# Bluetooth.net
KiCad netlist of a schematic drawn in Altium Designer
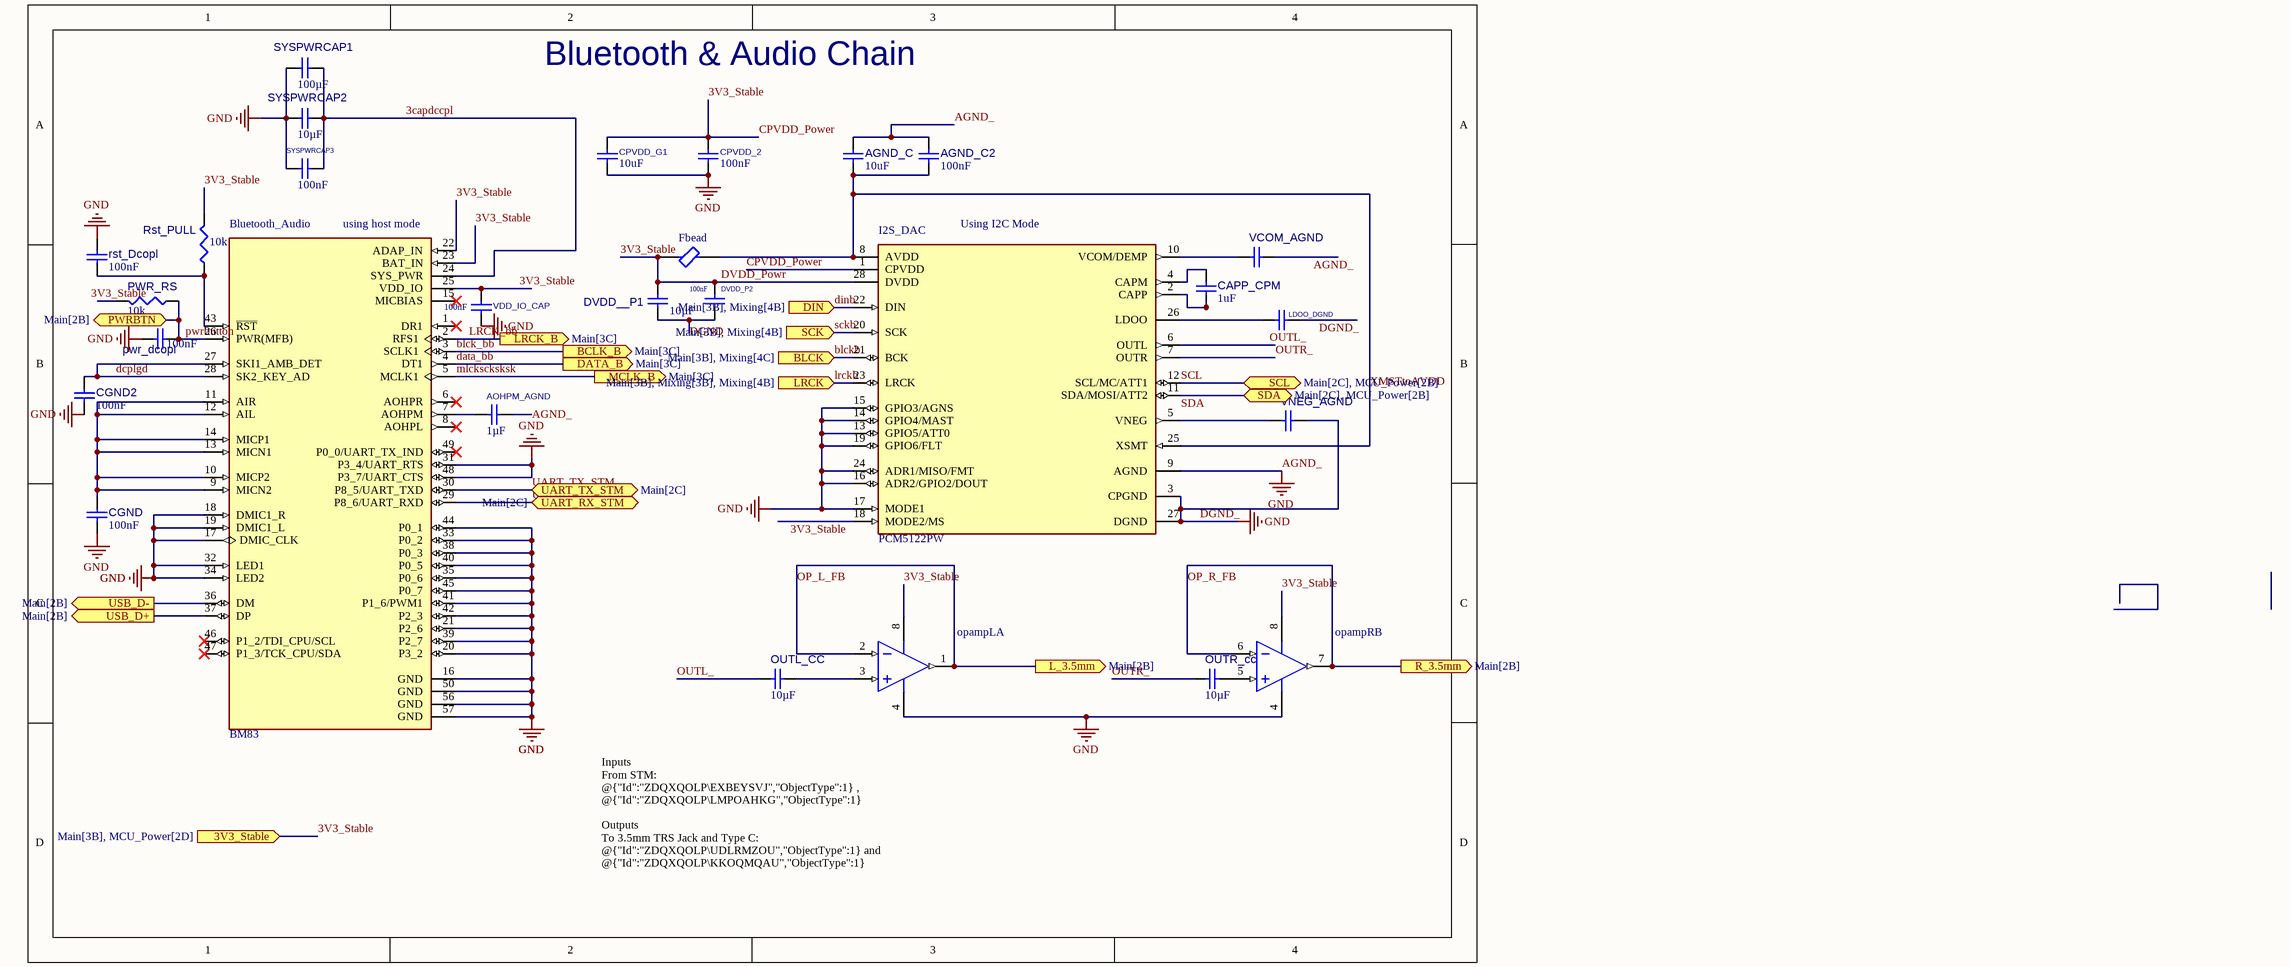
[diagram p0: Bluetooth.SchDoc]

(export (version "E")
  (design (tool "Eeschema 10.0.6"))
  (components
    (comp (ref "AGND_C")
      (value "10uF")
      (footprint "CAPC1005X56X25LL10T15")
      (description "Chip Capacitor, 0.1 uF, +/- 5%, 16 V, 0402 (1005 Metric)")
      (fields (field (name "TOLERANCE") "5%") (field (name "Comment") "Capacitor 0.1 uF +/- 5% 16 V 0402"))
      (libsource (lib "Sripathy Siddartha") (part "CAP-NP-2"))
    )
    (comp (ref "AGND_C2")
      (value "100nF")
      (footprint "CAPC0402(1005)60_L")
      (description "Chip Capacitor, 100nF +/-20%, 10V, 0402, Thickness 0.6 mm")
      (fields (field (name "TOLERANCE") "20%") (field (name "Comment") "Capacitor 100nF +/-20% 10V 0402"))
      (libsource (lib "Sripathy Siddartha") (part "CAP-NP-2"))
    )
    (comp (ref "AOHPM_AGND")
      (value "1µF")
      (footprint "CAPC2013X145X50ML20T25")
      (description "Chip Capacitor, 1 uF, +/-10%, 25 V, 0805 (2012 Metric)")
      (fields (field (name "TOLERANCE") "10%") (field (name "Comment") "Capacitor 1 uF +/- 10% 25 V 0805"))
      (libsource (lib "Sripathy Siddartha") (part "CAP-NP-2"))
    )
    (comp (ref "Bluetooth_Audio")
      (value "BM83")
      (footprint "XCVR_BM83SM1-00AA")
      (description "Bluetooth Bluetooth v5.0 Transceiver Module 2.4GHz ~ 2.48GHz PCB Trace Surface Mount")
      (fields (field (name "MP") "BM83SM1-00AA") (field (name "MF") "Microchip Technology"))
      (libsource (lib "Sripathy Siddartha") (part "BM83SM1-00AA"))
    )
    (comp (ref "CAPP_CPM")
      (value "1uF")
      (footprint "CAPC1005X56X25LL10T15")
      (description "Chip Capacitor, 0.1 uF, +/- 5%, 16 V, 0402 (1005 Metric)")
      (fields (field (name "TOLERANCE") "5%") (field (name "Comment") "Capacitor 0.1 uF +/- 5% 16 V 0402"))
      (libsource (lib "Sripathy Siddartha") (part "CAP-NP-2"))
    )
    (comp (ref "CGND")
      (value "100nF")
      (footprint "CAPC0402(1005)60_L")
      (description "Chip Capacitor, 100nF +/-20%, 10V, 0402, Thickness 0.6 mm")
      (fields (field (name "TOLERANCE") "20%") (field (name "Comment") "Capacitor 100nF +/-20% 10V 0402"))
      (libsource (lib "Sripathy Siddartha") (part "CAP-NP-2"))
    )
    (comp (ref "CGND2")
      (value "100nF")
      (footprint "CAPC0402(1005)60_L")
      (description "Chip Capacitor, 100nF +/-20%, 10V, 0402, Thickness 0.6 mm")
      (fields (field (name "TOLERANCE") "20%") (field (name "Comment") "Capacitor 100nF +/-20% 10V 0402"))
      (libsource (lib "Sripathy Siddartha") (part "CAP-NP-2"))
    )
    (comp (ref "CPVDD_2")
      (value "100nF")
      (footprint "CAPC0402(1005)60_L")
      (description "Chip Capacitor, 100nF +/-20%, 10V, 0402, Thickness 0.6 mm")
      (fields (field (name "TOLERANCE") "20%") (field (name "Comment") "Capacitor 100nF +/-20% 10V 0402"))
      (libsource (lib "Sripathy Siddartha") (part "CAP-NP-2"))
    )
    (comp (ref "CPVDD_G1")
      (value "10uF")
      (footprint "CAPC1005X56X25LL10T15")
      (description "Chip Capacitor, 0.1 uF, +/- 5%, 16 V, 0402 (1005 Metric)")
      (fields (field (name "TOLERANCE") "5%") (field (name "Comment") "Capacitor 0.1 uF +/- 5% 16 V 0402"))
      (libsource (lib "Sripathy Siddartha") (part "CAP-NP-2"))
    )
    (comp (ref "DVDD_P2")
      (value "100nF")
      (footprint "CAPC0402(1005)60_L")
      (description "Chip Capacitor, 100nF +/-20%, 10V, 0402, Thickness 0.6 mm")
      (fields (field (name "TOLERANCE") "20%") (field (name "Comment") "Capacitor 100nF +/-20% 10V 0402"))
      (libsource (lib "Sripathy Siddartha") (part "CAP-NP-2"))
    )
    (comp (ref "DVDD__P1")
      (value "10µF")
      (footprint "CAPC3216X180X50NL20T25")
      (description "Chip Capacitor, 10 uF, +/- 10%, 16 V, 1206 (3216 Metric)")
      (fields (field (name "TOLERANCE") "10%") (field (name "Comment") "Capacitor 10 uF +/- 10% 16 V 1206"))
      (libsource (lib "Sripathy Siddartha") (part "CAP-NP-2"))
    )
    (comp (ref "Fbead")
      (value "NFZ32BW3R6HZ10L")
      (footprint "FP-NFZ32BW-w2_8-MFG")
      (description "Ferrite Bead 3.6Ω @ 1MHz ±30% 2.55A 0.036Ω 1210 Embossed T/R")
      (libsource (lib "Altium Content Vault") (part "5f30dd21d616792df468990f7003faa"))
    )
    (comp (ref "I2S_DAC")
      (value "PCM5122PW")
      (footprint "FP-PW0028A-IPC_C")
      (description "IC DAC 16/24/32BIT 384K 28TSSOP")
      (libsource (lib "Altium Content Vault") (part "6849a3bd1951d5a6b717c470419a4c4"))
    )
    (comp (ref "LDOO_DGND")
      (value "Capacitor 0.1 uF +/- 5% 16 V 0402")
      (footprint "CAPC1005X56X25LL10T15")
      (description "Chip Capacitor, 0.1 uF, +/- 5%, 16 V, 0402 (1005 Metric)")
      (fields (field (name "TOLERANCE") "5%"))
      (libsource (lib "Sripathy Siddartha") (part "CAP-NP-2"))
    )
    (comp (ref "opampL")
      (value "OPA1612AIDR")
      (footprint "D0008A_N")
      (fields (field (name "MANUFACTURER") "Texas Instruments"))
      (libsource (lib "Altium Content Vault") (part "TI-OPA1612D8"))
    )
    (comp (ref "opampR")
      (value "OPA1612AIDR")
      (footprint "D0008A_N")
      (fields (field (name "MANUFACTURER") "Texas Instruments"))
      (libsource (lib "Altium Content Vault") (part "TI-OPA1612D8"))
    )
    (comp (ref "OUTL_CC")
      (value "10µF")
      (footprint "CAPC3216X180X50NL20T25")
      (description "Chip Capacitor, 10 uF, +/- 10%, 16 V, 1206 (3216 Metric)")
      (fields (field (name "TOLERANCE") "10%") (field (name "Comment") "Capacitor 10 uF +/- 10% 16 V 1206"))
      (libsource (lib "Sripathy Siddartha") (part "CAP-NP-2"))
    )
    (comp (ref "OUTR_cc")
      (value "10µF")
      (footprint "CAPC3216X180X50NL20T25")
      (description "Chip Capacitor, 10 uF, +/- 10%, 16 V, 1206 (3216 Metric)")
      (fields (field (name "TOLERANCE") "10%") (field (name "Comment") "Capacitor 10 uF +/- 10% 16 V 1206"))
      (libsource (lib "Sripathy Siddartha") (part "CAP-NP-2"))
    )
    (comp (ref "pwr_dcopl")
      (value "100nF")
      (footprint "CAPC0402(1005)60_L")
      (description "Chip Capacitor, 100nF +/-20%, 10V, 0402, Thickness 0.6 mm")
      (fields (field (name "TOLERANCE") "20%") (field (name "Comment") "Capacitor 100nF +/-20% 10V 0402"))
      (libsource (lib "Sripathy Siddartha") (part "CAP-NP-2"))
    )
    (comp (ref "PWR_RS")
      (value "10k")
      (footprint "RESC0402(1005)_L")
      (description "10K 0.063W 1% 0402 (1005 Metric)  SMD")
      (fields (field (name "POWER") "63mW") (field (name "TOLERANCE") "1%"))
      (libsource (lib "Sripathy Siddartha") (part "10KR2F"))
    )
    (comp (ref "rst_Dcopl")
      (value "100nF")
      (footprint "CAPC0402(1005)60_L")
      (description "Chip Capacitor, 100nF +/-20%, 10V, 0402, Thickness 0.6 mm")
      (fields (field (name "TOLERANCE") "20%") (field (name "Comment") "Capacitor 100nF +/-20% 10V 0402"))
      (libsource (lib "Sripathy Siddartha") (part "CAP-NP-2"))
    )
    (comp (ref "Rst_PULL")
      (value "10k")
      (footprint "RESC0402(1005)_L")
      (description "10K 0.063W 1% 0402 (1005 Metric)  SMD")
      (fields (field (name "POWER") "63mW") (field (name "TOLERANCE") "1%"))
      (libsource (lib "Sripathy Siddartha") (part "10KR2F"))
    )
    (comp (ref "SYSPWRCAP1")
      (value "100µF")
      (footprint "CAPC0805(2012)145_L")
      (description "Chip Capacitor, 100µF +/-20%, 6.3V, 0805, Thickness 1.45 mm")
      (fields (field (name "TOLERANCE") "10%") (field (name "Comment") "Capacitor 100µF +/-20% 6.3V 0805"))
      (libsource (lib "Sripathy Siddartha") (part "CAP-NP-2"))
    )
    (comp (ref "SYSPWRCAP2")
      (value "10µF")
      (footprint "CAPC0805(2012)145_L")
      (description "Chip Capacitor, 10µF +/-20%, 25V, 0805, Thickness 1.45 mm")
      (fields (field (name "TOLERANCE") "10%") (field (name "Comment") "Capacitor 10µF +/-20% 25V 0805"))
      (libsource (lib "Sripathy Siddartha") (part "CAP-NP-2"))
    )
    (comp (ref "SYSPWRCAP3")
      (value "100nF")
      (footprint "CAPC0402(1005)60_L")
      (description "Chip Capacitor, 100nF +/-20%, 50V, 0402, Thickness 0.6 mm")
      (fields (field (name "TOLERANCE") "10%") (field (name "Comment") "Capacitor 100nF +/-20% 50V 0402"))
      (libsource (lib "Sripathy Siddartha") (part "CAP-NP-2"))
    )
    (comp (ref "VCOM_AGND")
      (value "Capacitor 0.1 uF +/- 5% 16 V 0402")
      (footprint "CAPC1005X56X25LL10T15")
      (description "Chip Capacitor, 0.1 uF, +/- 5%, 16 V, 0402 (1005 Metric)")
      (fields (field (name "TOLERANCE") "5%"))
      (libsource (lib "Sripathy Siddartha") (part "CAP-NP-2"))
    )
    (comp (ref "VDD_IO_CAP")
      (value "100nF")
      (footprint "CAPC0402(1005)60_L")
      (description "Chip Capacitor, 100nF +/-20%, 25V, 0402, Thickness 0.6 mm")
      (fields (field (name "TOLERANCE") "10%") (field (name "Comment") "Capacitor 100nF +/-20% 25V 0402"))
      (libsource (lib "Sripathy Siddartha") (part "CAP-NP-2"))
    )
    (comp (ref "VNEG_AGND")
      (value "Capacitor 0.1 uF +/- 5% 16 V 0402")
      (footprint "CAPC1005X56X25LL10T15")
      (description "Chip Capacitor, 0.1 uF, +/- 5%, 16 V, 0402 (1005 Metric)")
      (fields (field (name "TOLERANCE") "5%"))
      (libsource (lib "Sripathy Siddartha") (part "CAP-NP-2"))
    )
  )
  (nets
    (net (code "1") (name "/3V3_Stable") (class "Default")
      (node (ref "Bluetooth_Audio") (pin "22") (pinfunction "ADAP_IN_22") (pintype "input"))
      (node (ref "Bluetooth_Audio") (pin "23") (pinfunction "BAT_IN_23") (pintype "input"))
      (node (ref "Bluetooth_Audio") (pin "25") (pinfunction "VDD_IO_25") (pintype "power_in"))
      (node (ref "CPVDD_2") (pin "2") (pinfunction "2_2") (pintype "passive"))
      (node (ref "CPVDD_G1") (pin "1") (pinfunction "1_1") (pintype "passive"))
      (node (ref "DVDD_P2") (pin "2") (pinfunction "2_2") (pintype "passive"))
      (node (ref "DVDD__P1") (pin "2") (pinfunction "2_2") (pintype "passive"))
      (node (ref "Fbead") (pin "1") (pinfunction "1_1") (pintype "passive"))
      (node (ref "I2S_DAC") (pin "1") (pinfunction "CPVDD_1") (pintype "power_in"))
      (node (ref "I2S_DAC") (pin "18") (pinfunction "MODE2/MS_18") (pintype "input"))
      (node (ref "I2S_DAC") (pin "28") (pinfunction "DVDD_28") (pintype "power_in"))
      (node (ref "Rst_PULL") (pin "2") (pinfunction "2_2") (pintype "passive"))
      (node (ref "VDD_IO_CAP") (pin "2") (pinfunction "2_2") (pintype "passive"))
      (node (ref "opampL") (pin "8") (pinfunction "V+_8") (pintype "power_in"))
      (node (ref "opampR") (pin "8") (pinfunction "V+_8") (pintype "power_in"))
    )
    (net (code "2") (name "/3capdccpl") (class "Default")
      (node (ref "Bluetooth_Audio") (pin "24") (pinfunction "SYS_PWR_24") (pintype "power_in"))
      (node (ref "SYSPWRCAP1") (pin "2") (pinfunction "2_2") (pintype "passive"))
      (node (ref "SYSPWRCAP2") (pin "2") (pinfunction "2_2") (pintype "passive"))
      (node (ref "SYSPWRCAP3") (pin "2") (pinfunction "2_2") (pintype "passive"))
    )
    (net (code "4") (name "/LRCK_bb") (class "Default")
      (node (ref "Bluetooth_Audio") (pin "2") (pinfunction "RFS1_2") (pintype "bidirectional"))
    )
    (net (code "5") (name "/OP_L_FB") (class "Default")
      (node (ref "opampL") (pin "1") (pinfunction "OUT_A_1") (pintype "output"))
      (node (ref "opampL") (pin "2") (pinfunction "IN_A-_2") (pintype "input"))
    )
    (net (code "6") (name "/OP_R_FB") (class "Default")
      (node (ref "opampR") (pin "6") (pinfunction "IN_B-_6") (pintype "input"))
      (node (ref "opampR") (pin "7") (pinfunction "OUT_B_7") (pintype "output"))
    )
    (net (code "7") (name "/OUTL_") (class "Default")
      (node (ref "I2S_DAC") (pin "6") (pinfunction "OUTL_6") (pintype "output"))
      (node (ref "OUTL_CC") (pin "1") (pinfunction "1_1") (pintype "passive"))
    )
    (net (code "8") (name "/OUTR_") (class "Default")
      (node (ref "I2S_DAC") (pin "7") (pinfunction "OUTR_7") (pintype "output"))
      (node (ref "OUTR_cc") (pin "1") (pinfunction "1_1") (pintype "passive"))
    )
    (net (code "9") (name "/SCL") (class "Default")
      (node (ref "I2S_DAC") (pin "12") (pinfunction "SCL/MC/ATT1_12") (pintype "bidirectional"))
    )
    (net (code "10") (name "/SDA") (class "Default")
      (node (ref "I2S_DAC") (pin "11") (pinfunction "SDA/MOSI/ATT2_11") (pintype "bidirectional"))
    )
    (net (code "11") (name "/UART_RX_STM") (class "Default")
      (node (ref "Bluetooth_Audio") (pin "29") (pinfunction "P8_6/UART_RXD_29") (pintype "bidirectional"))
    )
    (net (code "12") (name "/UART_TX_STM") (class "Default")
      (node (ref "Bluetooth_Audio") (pin "30") (pinfunction "P8_5/UART_TXD_30") (pintype "bidirectional"))
    )
    (net (code "13") (name "/USB_D+") (class "Default")
      (node (ref "Bluetooth_Audio") (pin "37") (pinfunction "DP_37") (pintype "bidirectional"))
    )
    (net (code "14") (name "/USB_D-") (class "Default")
      (node (ref "Bluetooth_Audio") (pin "36") (pinfunction "DM_36") (pintype "bidirectional"))
    )
    (net (code "15") (name "/XMSTtoAVDD") (class "Default")
      (node (ref "AGND_C") (pin "1") (pinfunction "1_1") (pintype "passive"))
      (node (ref "AGND_C2") (pin "2") (pinfunction "2_2") (pintype "passive"))
      (node (ref "Fbead") (pin "2") (pinfunction "2_2") (pintype "passive"))
      (node (ref "I2S_DAC") (pin "25") (pinfunction "XSMT_25") (pintype "input"))
      (node (ref "I2S_DAC") (pin "8") (pinfunction "AVDD_8") (pintype "power_in"))
    )
    (net (code "16") (name "/blck_bb") (class "Default")
      (node (ref "Bluetooth_Audio") (pin "3") (pinfunction "SCLK1_3") (pintype "bidirectional"))
    )
    (net (code "17") (name "/blckb") (class "Default")
      (node (ref "I2S_DAC") (pin "21") (pinfunction "BCK_21") (pintype "bidirectional"))
    )
    (net (code "18") (name "/data_bb") (class "Default")
      (node (ref "Bluetooth_Audio") (pin "4") (pinfunction "DT1_4") (pintype "output"))
    )
    (net (code "19") (name "/dcplgd") (class "Default")
      (node (ref "Bluetooth_Audio") (pin "27") (pinfunction "SKI1_AMB_DET_27") (pintype "input"))
      (node (ref "Bluetooth_Audio") (pin "28") (pinfunction "SK2_KEY_AD_28") (pintype "input"))
      (node (ref "CGND2") (pin "2") (pinfunction "2_2") (pintype "passive"))
    )
    (net (code "20") (name "/dinb") (class "Default")
      (node (ref "I2S_DAC") (pin "22") (pinfunction "DIN_22") (pintype "input"))
    )
    (net (code "21") (name "/lrckb") (class "Default")
      (node (ref "I2S_DAC") (pin "23") (pinfunction "LRCK_23") (pintype "bidirectional"))
    )
    (net (code "22") (name "/mlckscksksk") (class "Default")
      (node (ref "Bluetooth_Audio") (pin "5") (pinfunction "MCLK1_5") (pintype "output"))
    )
    (net (code "23") (name "/pwrbutton") (class "Default")
      (node (ref "Bluetooth_Audio") (pin "26") (pinfunction "PWR(MFB)_26") (pintype "input"))
      (node (ref "PWR_RS") (pin "1") (pinfunction "1_1") (pintype "passive"))
      (node (ref "pwr_dcopl") (pin "2") (pinfunction "2_2") (pintype "passive"))
    )
    (net (code "24") (name "/sckb") (class "Default")
      (node (ref "I2S_DAC") (pin "20") (pinfunction "SCK_20") (pintype "input"))
    )
    (net (code "25") (name "GND") (class "Default")
      (node (ref "AGND_C") (pin "2") (pinfunction "2_2") (pintype "passive"))
      (node (ref "AGND_C2") (pin "1") (pinfunction "1_1") (pintype "passive"))
      (node (ref "AOHPM_AGND") (pin "2") (pinfunction "2_2") (pintype "passive"))
      (node (ref "Bluetooth_Audio") (pin "16") (pinfunction "GND_16") (pintype "power_in"))
      (node (ref "Bluetooth_Audio") (pin "17") (pinfunction "DMIC_CLK_17") (pintype "output"))
      (node (ref "Bluetooth_Audio") (pin "18") (pinfunction "DMIC1_R_18") (pintype "input"))
      (node (ref "Bluetooth_Audio") (pin "19") (pinfunction "DMIC1_L_19") (pintype "input"))
      (node (ref "Bluetooth_Audio") (pin "20") (pinfunction "P3_2_20") (pintype "bidirectional"))
      (node (ref "Bluetooth_Audio") (pin "21") (pinfunction "P2_6_21") (pintype "bidirectional"))
      (node (ref "Bluetooth_Audio") (pin "31") (pinfunction "P3_4/UART_RTS_31") (pintype "bidirectional"))
      (node (ref "Bluetooth_Audio") (pin "32") (pinfunction "LED1_32") (pintype "input"))
      (node (ref "Bluetooth_Audio") (pin "33") (pinfunction "P0_2_33") (pintype "bidirectional"))
      (node (ref "Bluetooth_Audio") (pin "34") (pinfunction "LED2_34") (pintype "input"))
      (node (ref "Bluetooth_Audio") (pin "35") (pinfunction "P0_6_35") (pintype "bidirectional"))
      (node (ref "Bluetooth_Audio") (pin "38") (pinfunction "P0_3_38") (pintype "bidirectional"))
      (node (ref "Bluetooth_Audio") (pin "39") (pinfunction "P2_7_39") (pintype "bidirectional"))
      (node (ref "Bluetooth_Audio") (pin "40") (pinfunction "P0_5_40") (pintype "bidirectional"))
      (node (ref "Bluetooth_Audio") (pin "41") (pinfunction "P1_6/PWM1_41") (pintype "bidirectional"))
      (node (ref "Bluetooth_Audio") (pin "42") (pinfunction "P2_3_42") (pintype "bidirectional"))
      (node (ref "Bluetooth_Audio") (pin "44") (pinfunction "P0_1_44") (pintype "bidirectional"))
      (node (ref "Bluetooth_Audio") (pin "45") (pinfunction "P0_7_45") (pintype "bidirectional"))
      (node (ref "Bluetooth_Audio") (pin "48") (pinfunction "P3_7/UART_CTS_48") (pintype "bidirectional"))
      (node (ref "Bluetooth_Audio") (pin "50") (pinfunction "GND_50") (pintype "power_in"))
      (node (ref "Bluetooth_Audio") (pin "56") (pinfunction "GND_56") (pintype "power_in"))
      (node (ref "Bluetooth_Audio") (pin "57") (pinfunction "GND_57") (pintype "power_in"))
      (node (ref "CGND") (pin "1") (pinfunction "1_1") (pintype "passive"))
      (node (ref "CGND2") (pin "1") (pinfunction "1_1") (pintype "passive"))
      (node (ref "CPVDD_2") (pin "1") (pinfunction "1_1") (pintype "passive"))
      (node (ref "CPVDD_G1") (pin "2") (pinfunction "2_2") (pintype "passive"))
      (node (ref "I2S_DAC") (pin "13") (pinfunction "GPIO5/ATT0_13") (pintype "bidirectional"))
      (node (ref "I2S_DAC") (pin "14") (pinfunction "GPIO4/MAST_14") (pintype "bidirectional"))
      (node (ref "I2S_DAC") (pin "15") (pinfunction "GPIO3/AGNS_15") (pintype "bidirectional"))
      (node (ref "I2S_DAC") (pin "16") (pinfunction "ADR2/GPIO2/DOUT_16") (pintype "bidirectional"))
      (node (ref "I2S_DAC") (pin "17") (pinfunction "MODE1_17") (pintype "input"))
      (node (ref "I2S_DAC") (pin "19") (pinfunction "GPIO6/FLT_19") (pintype "bidirectional"))
      (node (ref "I2S_DAC") (pin "24") (pinfunction "ADR1/MISO/FMT_24") (pintype "bidirectional"))
      (node (ref "I2S_DAC") (pin "27") (pinfunction "DGND_27") (pintype "power_in"))
      (node (ref "I2S_DAC") (pin "3") (pinfunction "CPGND_3") (pintype "power_in"))
      (node (ref "I2S_DAC") (pin "9") (pinfunction "AGND_9") (pintype "power_in"))
      (node (ref "LDOO_DGND") (pin "2") (pinfunction "2_2") (pintype "passive"))
      (node (ref "SYSPWRCAP1") (pin "1") (pinfunction "1_1") (pintype "passive"))
      (node (ref "SYSPWRCAP2") (pin "1") (pinfunction "1_1") (pintype "passive"))
      (node (ref "SYSPWRCAP3") (pin "1") (pinfunction "1_1") (pintype "passive"))
      (node (ref "VCOM_AGND") (pin "2") (pinfunction "2_2") (pintype "passive"))
      (node (ref "VDD_IO_CAP") (pin "1") (pinfunction "1_1") (pintype "passive"))
      (node (ref "VNEG_AGND") (pin "2") (pinfunction "2_2") (pintype "passive"))
      (node (ref "opampL") (pin "4") (pinfunction "V-_4") (pintype "power_in"))
      (node (ref "opampR") (pin "4") (pinfunction "V-_4") (pintype "power_in"))
      (node (ref "pwr_dcopl") (pin "1") (pinfunction "1_1") (pintype "passive"))
      (node (ref "rst_Dcopl") (pin "1") (pinfunction "1_1") (pintype "passive"))
    )
    (net (code "26") (name "Net-(Bluetooth_Audio-AIL)") (class "Default")
      (node (ref "Bluetooth_Audio") (pin "10") (pinfunction "MICP2_10") (pintype "input"))
      (node (ref "Bluetooth_Audio") (pin "11") (pinfunction "AIR_11") (pintype "input"))
      (node (ref "Bluetooth_Audio") (pin "12") (pinfunction "AIL_12") (pintype "input"))
      (node (ref "Bluetooth_Audio") (pin "13") (pinfunction "MICN1_13") (pintype "input"))
      (node (ref "Bluetooth_Audio") (pin "14") (pinfunction "MICP1_14") (pintype "input"))
      (node (ref "Bluetooth_Audio") (pin "9") (pinfunction "MICN2_9") (pintype "input"))
      (node (ref "CGND") (pin "2") (pinfunction "2_2") (pintype "passive"))
    )
    (net (code "27") (name "Net-(Bluetooth_Audio-AOHPM)") (class "Default")
      (node (ref "AOHPM_AGND") (pin "1") (pinfunction "1_1") (pintype "passive"))
      (node (ref "Bluetooth_Audio") (pin "7") (pinfunction "AOHPM_7") (pintype "output"))
    )
    (net (code "28") (name "Net-(Bluetooth_Audio-~{RST})") (class "Default")
      (node (ref "Bluetooth_Audio") (pin "43") (pinfunction "~{RST}_43") (pintype "input"))
      (node (ref "Rst_PULL") (pin "1") (pinfunction "1_1") (pintype "passive"))
      (node (ref "rst_Dcopl") (pin "2") (pinfunction "2_2") (pintype "passive"))
    )
    (net (code "29") (name "Net-(DVDD_P2-Pad1)") (class "Default")
      (node (ref "DVDD_P2") (pin "1") (pinfunction "1_1") (pintype "passive"))
      (node (ref "DVDD__P1") (pin "1") (pinfunction "1_1") (pintype "passive"))
    )
    (net (code "30") (name "Net-(I2S_DAC-CAPM)") (class "Default")
      (node (ref "CAPP_CPM") (pin "2") (pinfunction "2_2") (pintype "passive"))
      (node (ref "I2S_DAC") (pin "4") (pinfunction "CAPM_4") (pintype "output"))
    )
    (net (code "31") (name "Net-(I2S_DAC-CAPP)") (class "Default")
      (node (ref "CAPP_CPM") (pin "1") (pinfunction "1_1") (pintype "passive"))
      (node (ref "I2S_DAC") (pin "2") (pinfunction "CAPP_2") (pintype "output"))
    )
    (net (code "32") (name "Net-(I2S_DAC-LDOO)") (class "Default")
      (node (ref "I2S_DAC") (pin "26") (pinfunction "LDOO_26") (pintype "power_in"))
      (node (ref "LDOO_DGND") (pin "1") (pinfunction "1_1") (pintype "passive"))
    )
    (net (code "33") (name "Net-(I2S_DAC-VCOM{slash}DEMP)") (class "Default")
      (node (ref "I2S_DAC") (pin "10") (pinfunction "VCOM/DEMP_10") (pintype "output"))
      (node (ref "VCOM_AGND") (pin "1") (pinfunction "1_1") (pintype "passive"))
    )
    (net (code "34") (name "Net-(I2S_DAC-VNEG)") (class "Default")
      (node (ref "I2S_DAC") (pin "5") (pinfunction "VNEG_5") (pintype "output"))
      (node (ref "VNEG_AGND") (pin "1") (pinfunction "1_1") (pintype "passive"))
    )
    (net (code "35") (name "Net-(opampLA-IN_A+)") (class "Default")
      (node (ref "OUTL_CC") (pin "2") (pinfunction "2_2") (pintype "passive"))
      (node (ref "opampL") (pin "3") (pinfunction "IN_A+_3") (pintype "input"))
    )
    (net (code "36") (name "Net-(opampRB-IN_B+)") (class "Default")
      (node (ref "OUTR_cc") (pin "2") (pinfunction "2_2") (pintype "passive"))
      (node (ref "opampR") (pin "5") (pinfunction "IN_B+_5") (pintype "input"))
    )
    (net (code "37") (name "unconnected-(Bluetooth_Audio-AOHPL-Pad8)") (class "Default")
      (node (ref "Bluetooth_Audio") (pin "8") (pinfunction "AOHPL_8") (pintype "output+no_connect"))
    )
    (net (code "38") (name "unconnected-(Bluetooth_Audio-AOHPR-Pad6)") (class "Default")
      (node (ref "Bluetooth_Audio") (pin "6") (pinfunction "AOHPR_6") (pintype "output+no_connect"))
    )
    (net (code "39") (name "unconnected-(Bluetooth_Audio-DR1-Pad1)") (class "Default")
      (node (ref "Bluetooth_Audio") (pin "1") (pinfunction "DR1_1") (pintype "input+no_connect"))
    )
    (net (code "40") (name "unconnected-(Bluetooth_Audio-MICBIAS-Pad15)") (class "Default")
      (node (ref "Bluetooth_Audio") (pin "15") (pinfunction "MICBIAS_15") (pintype "power_in+no_connect"))
    )
    (net (code "41") (name "unconnected-(Bluetooth_Audio-P0_0{slash}UART_TX_IND-Pad49)") (class "Default")
      (node (ref "Bluetooth_Audio") (pin "49") (pinfunction "P0_0/UART_TX_IND_49") (pintype "bidirectional+no_connect"))
    )
    (net (code "42") (name "unconnected-(Bluetooth_Audio-P1_2{slash}TDI_CPU{slash}SCL-Pad46)") (class "Default")
      (node (ref "Bluetooth_Audio") (pin "46") (pinfunction "P1_2/TDI_CPU/SCL_46") (pintype "bidirectional+no_connect"))
    )
    (net (code "43") (name "unconnected-(Bluetooth_Audio-P1_3{slash}TCK_CPU{slash}SDA-Pad47)") (class "Default")
      (node (ref "Bluetooth_Audio") (pin "47") (pinfunction "P1_3/TCK_CPU/SDA_47") (pintype "bidirectional+no_connect"))
    )
    (net (code "44") (name "unconnected-(PWR_RS-Pad2)") (class "Default")
      (node (ref "PWR_RS") (pin "2") (pinfunction "2_2") (pintype "passive"))
    )
  )
)
